# USBPD_CH211.net
KiCad netlist of a schematic drawn in Altium Designer
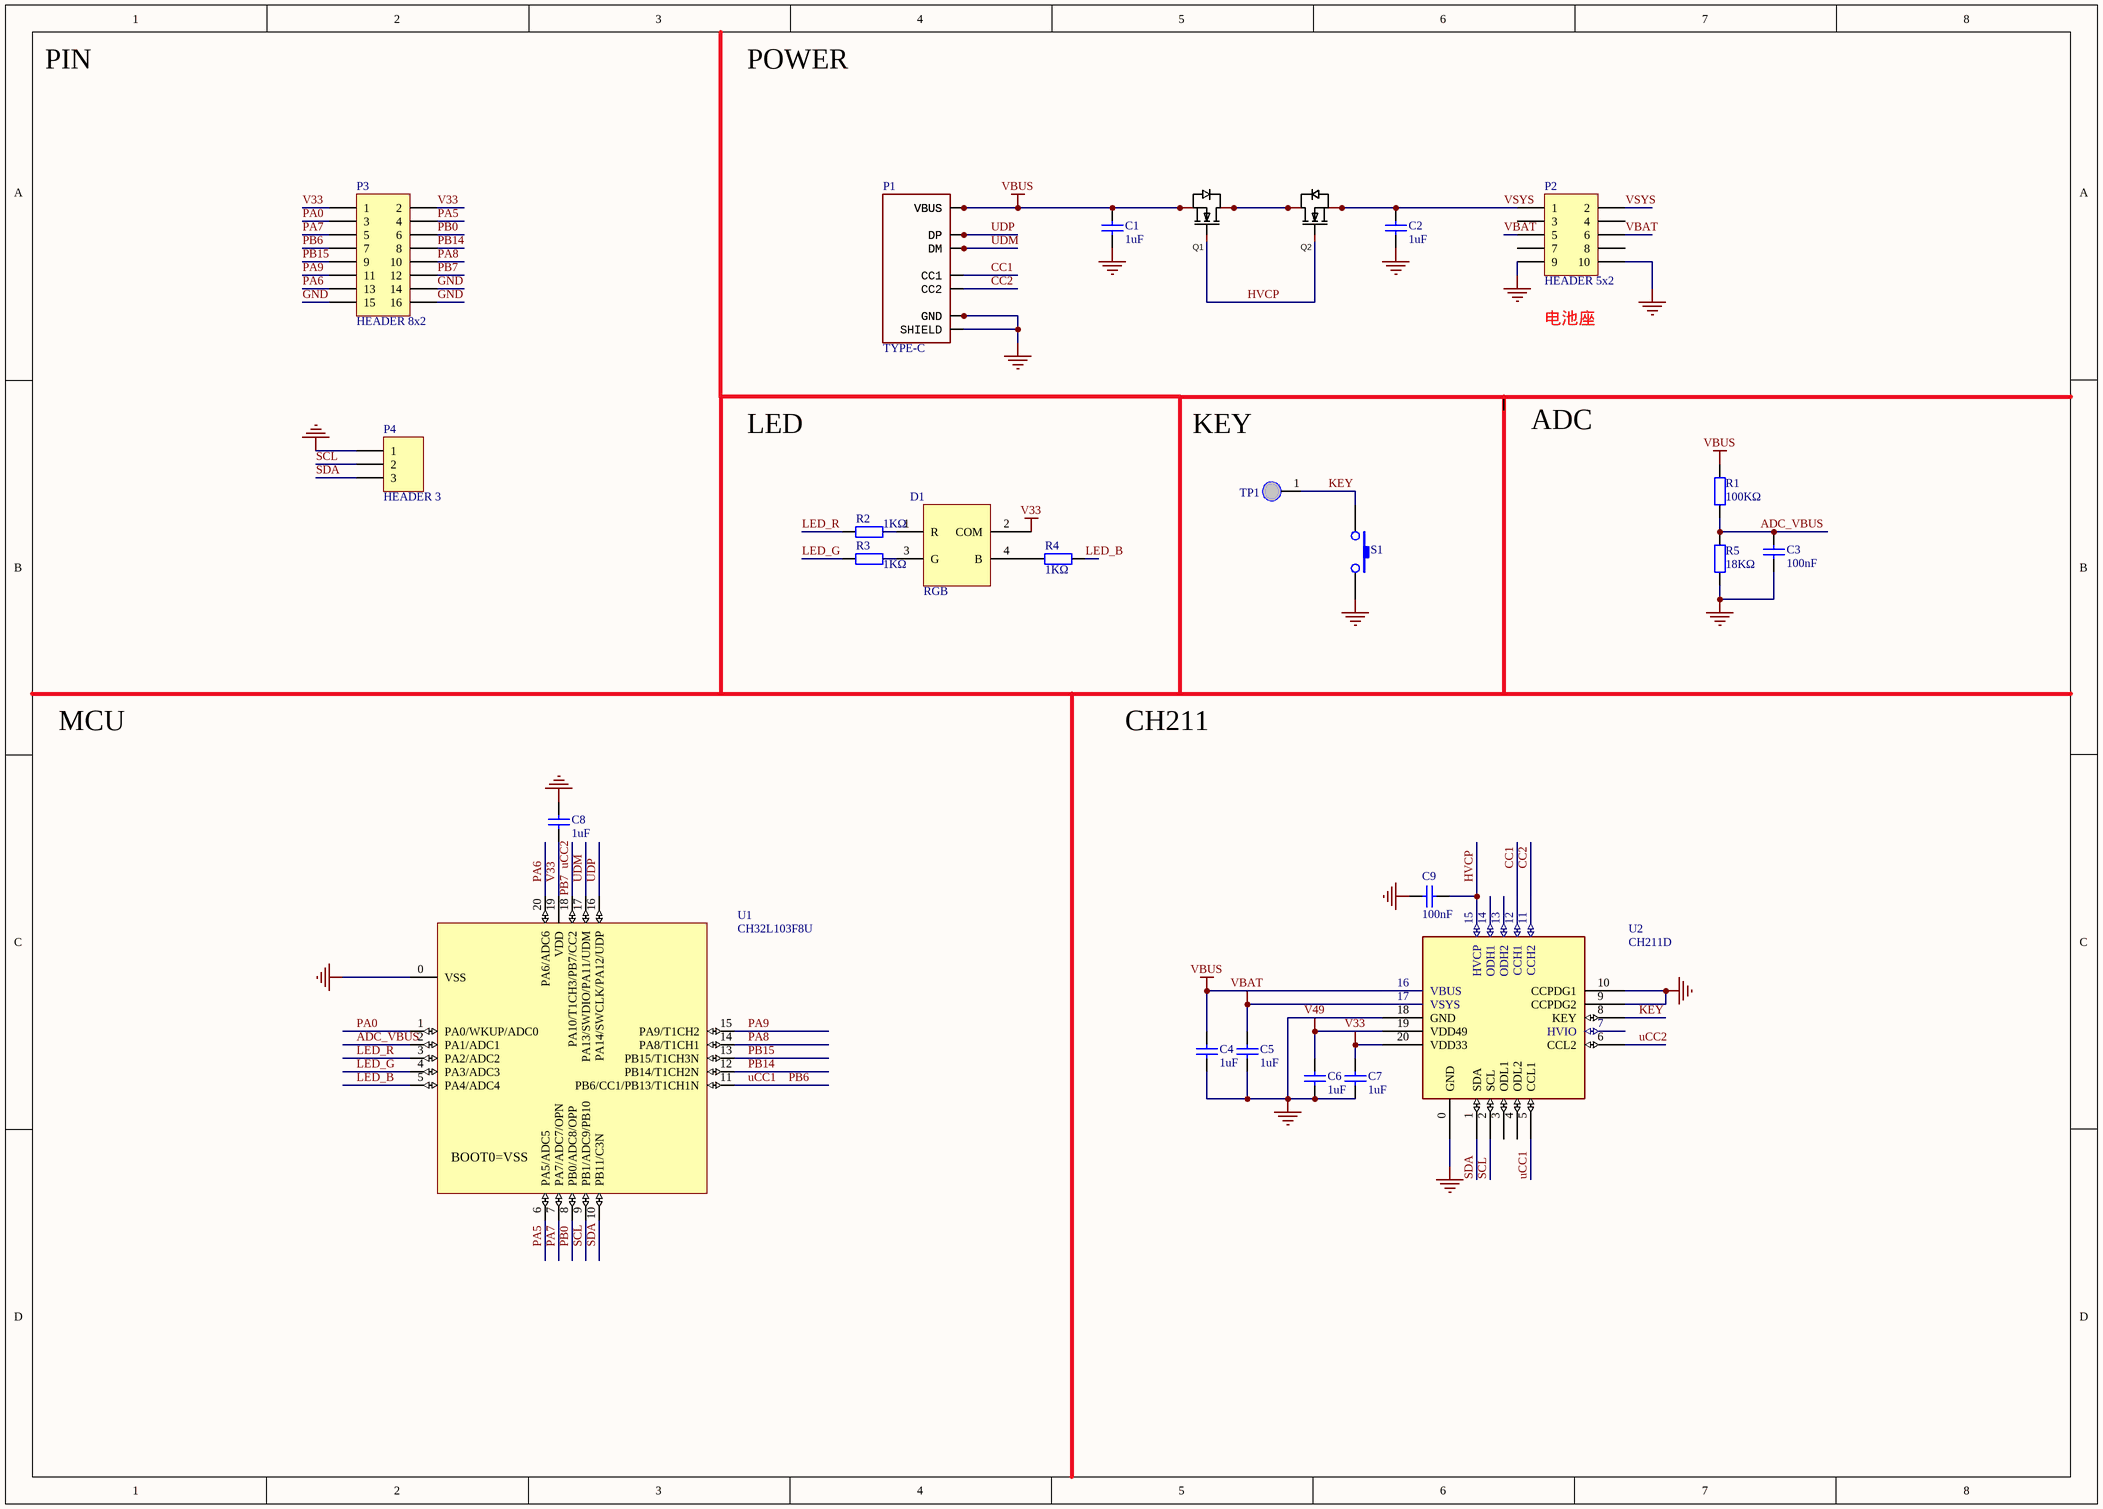
[diagram p0: USBPD_CH211.SchDoc]

(export (version "E")
  (design (tool "Eeschema 10.0.6"))
  (components
    (comp (ref "C1")
      (value "1uF")
      (footprint "0402_C")
      (description "贴片电容")
      (libsource (lib "Miscellaneous Devices LC") (part "0603 100nF (104) 10% 50V"))
    )
    (comp (ref "C2")
      (value "1uF")
      (footprint "0402_C")
      (description "贴片电容")
      (libsource (lib "Miscellaneous Devices LC") (part "0603 100nF (104) 10% 50V"))
    )
    (comp (ref "C3")
      (value "100nF")
      (footprint "0402_C")
      (description "贴片电容")
      (libsource (lib "Miscellaneous Devices LC") (part "0603 100nF (104) 10% 50V"))
    )
    (comp (ref "C4")
      (value "1uF")
      (footprint "0402_C")
      (description "贴片电容")
      (libsource (lib "Miscellaneous Devices LC") (part "0603 100nF (104) 10% 50V"))
    )
    (comp (ref "C5")
      (value "1uF")
      (footprint "0402_C")
      (description "贴片电容")
      (libsource (lib "Miscellaneous Devices LC") (part "0603 100nF (104) 10% 50V"))
    )
    (comp (ref "C6")
      (value "1uF")
      (footprint "0402_C")
      (description "贴片电容")
      (libsource (lib "Miscellaneous Devices LC") (part "0603 100nF (104) 10% 50V"))
    )
    (comp (ref "C7")
      (value "1uF")
      (footprint "0402_C")
      (description "贴片电容")
      (libsource (lib "Miscellaneous Devices LC") (part "0603 100nF (104) 10% 50V"))
    )
    (comp (ref "C8")
      (value "1uF")
      (footprint "0402_C")
      (description "贴片电容")
      (libsource (lib "Miscellaneous Devices LC") (part "0603 1uF (105) 10% 50V"))
    )
    (comp (ref "C9")
      (value "100nF")
      (footprint "0402_C")
      (description "贴片电容")
      (libsource (lib "Miscellaneous Devices LC") (part "0603 100nF (104) 10% 50V"))
    )
    (comp (ref "D1")
      (value "RGB")
      (footprint "RGB")
      (description "共阳")
      (libsource (lib "wch_sch_others") (part "RGB"))
    )
    (comp (ref "P1")
      (value "TYPE-C")
      (footprint "TYPE-C-Receptacle-2.0")
      (libsource (lib "Miscellaneous SCH Lib") (part "TYPE-C-Receptacle-RefDesign"))
    )
    (comp (ref "P2")
      (value "HEADER 5x2")
      (footprint "MYPCB:IDC10-2.54mm")
      (description "Header, 5-Pin, Dual row")
      (libsource (lib "wch_sch_others") (part "HEADER 5x2"))
    )
    (comp (ref "P3")
      (value "HEADER 8x2")
      (footprint "MYPCB:IDC16-2.54mm")
      (description "Header, 8-Pin, Dual row")
      (libsource (lib "wch_sch_others") (part "HEADER 8x2"))
    )
    (comp (ref "P4")
      (value "HEADER 3")
      (footprint "SIP3-2.54MM")
      (description "Header, 3-Pin")
      (libsource (lib "wch_sch_others") (part "HEADER 3"))
    )
    (comp (ref "Q1")
      (value "ASDM40N52E-R")
      (footprint "DFN-8_L3.1-W3.0-P0.65-LS3.3-BL")
      (description "DFN_NMOS")
      (fields (field (name "MANUFACTURER") "Ascend(安森德)"))
      (libsource (lib "Zcc") (part "NMOS_DFN3*3.1"))
    )
    (comp (ref "Q2")
      (value "ASDM40N52E-R")
      (footprint "DFN-8_L3.1-W3.0-P0.65-LS3.3-BL")
      (description "DFN_NMOS")
      (fields (field (name "MANUFACTURER") "Ascend(安森德)"))
      (libsource (lib "Zcc") (part "NMOS_DFN3*3.1"))
    )
    (comp (ref "R1")
      (value "100KΩ")
      (footprint "0402")
      (description "贴片电阻")
      (libsource (lib "Miscellaneous Devices LC") (part "0603 100KΩ (1003) 1%"))
    )
    (comp (ref "R2")
      (value "1KΩ")
      (footprint "0402")
      (description "贴片电阻")
      (libsource (lib "") (part "0603 100KΩ (1003) 1%_1"))
    )
    (comp (ref "R3")
      (value "1KΩ")
      (footprint "0402")
      (description "贴片电阻")
      (libsource (lib "") (part "0603 100KΩ (1003) 1%_1"))
    )
    (comp (ref "R4")
      (value "1KΩ")
      (footprint "0402")
      (description "贴片电阻")
      (libsource (lib "") (part "0603 100KΩ (1003) 1%_1"))
    )
    (comp (ref "R5")
      (value "18KΩ")
      (footprint "0402")
      (description "贴片电阻")
      (libsource (lib "Miscellaneous Devices LC") (part "0603 100KΩ (1003) 1%"))
    )
    (comp (ref "S1")
      (value "KEY")
      (footprint "SMD_6.1x3.65x2.5mm-KEY")
      (libsource (lib "wch_sch_others") (part "KEY1"))
    )
    (comp (ref "TP1")
      (value "Testpoint")
      (footprint "TESTPOINT3")
      (description "测试点")
      (libsource (lib "wch_sch_others") (part "Testpoint"))
    )
    (comp (ref "U1")
      (value "CH32L103F8U")
      (footprint "QFN20_3X3")
      (description "RISC-V LMD-MCU, 96MHz, USB, Type-C/PD-5K1, CAN, OPA, lower power")
      (libsource (lib "CHXXX") (part "CH32L103F8U"))
    )
    (comp (ref "U2")
      (value "CH211D")
      (footprint "QFN20_3X3")
      (description "28V USB PD & Type-C high voltage interface")
      (libsource (lib "CHXXX") (part "CH211D"))
    )
  )
  (nets
    (net (code "1") (name "/ADC_VBUS") (class "Default")
      (node (ref "C3") (pin "2") (pinfunction "2_2") (pintype "passive"))
      (node (ref "R1") (pin "2") (pinfunction "2_2") (pintype "passive"))
      (node (ref "R5") (pin "1") (pinfunction "1_1") (pintype "passive"))
      (node (ref "U1") (pin "2") (pinfunction "PA1/ADC1_2") (pintype "bidirectional"))
    )
    (net (code "2") (name "/CC1") (class "Default")
      (node (ref "P1") (pin "A5") (pinfunction "CC1_A5") (pintype "passive"))
      (node (ref "U2") (pin "12") (pinfunction "CCH1_12") (pintype "bidirectional"))
    )
    (net (code "3") (name "/CC2") (class "Default")
      (node (ref "P1") (pin "B5") (pinfunction "CC2_B5") (pintype "passive"))
      (node (ref "U2") (pin "11") (pinfunction "CCH2_11") (pintype "bidirectional"))
    )
    (net (code "4") (name "/HVCP") (class "Default")
      (node (ref "C9") (pin "1") (pinfunction "1_1") (pintype "passive"))
      (node (ref "Q1") (pin "4") (pinfunction "G_4") (pintype "passive"))
      (node (ref "Q2") (pin "4") (pinfunction "G_4") (pintype "passive"))
      (node (ref "U2") (pin "15") (pinfunction "HVCP_15") (pintype "bidirectional"))
    )
    (net (code "5") (name "/KEY") (class "Default")
      (node (ref "S1") (pin "1") (pinfunction "1_1") (pintype "passive"))
      (node (ref "TP1") (pin "1") (pintype "passive"))
      (node (ref "U2") (pin "8") (pinfunction "KEY_8") (pintype "bidirectional"))
    )
    (net (code "6") (name "/LED_B") (class "Default")
      (node (ref "R4") (pin "2") (pinfunction "2_2") (pintype "passive"))
      (node (ref "U1") (pin "5") (pinfunction "PA4/ADC4_5") (pintype "bidirectional"))
    )
    (net (code "7") (name "/LED_G") (class "Default")
      (node (ref "R3") (pin "1") (pinfunction "1_1") (pintype "passive"))
      (node (ref "U1") (pin "4") (pinfunction "PA3/ADC3_4") (pintype "bidirectional"))
    )
    (net (code "8") (name "/LED_R") (class "Default")
      (node (ref "R2") (pin "1") (pinfunction "1_1") (pintype "passive"))
      (node (ref "U1") (pin "3") (pinfunction "PA2/ADC2_3") (pintype "bidirectional"))
    )
    (net (code "9") (name "/PA0") (class "Default")
      (node (ref "P3") (pin "3") (pinfunction "3_3") (pintype "passive"))
      (node (ref "U1") (pin "1") (pinfunction "PA0/WKUP/ADC0_1") (pintype "bidirectional"))
    )
    (net (code "10") (name "/PA5") (class "Default")
      (node (ref "P3") (pin "4") (pinfunction "4_4") (pintype "passive"))
      (node (ref "U1") (pin "6") (pinfunction "PA5/ADC5_6") (pintype "bidirectional"))
    )
    (net (code "11") (name "/PA6") (class "Default")
      (node (ref "P3") (pin "13") (pinfunction "13_13") (pintype "passive"))
      (node (ref "U1") (pin "20") (pinfunction "PA6/ADC6_20") (pintype "bidirectional"))
    )
    (net (code "12") (name "/PA7") (class "Default")
      (node (ref "P3") (pin "5") (pinfunction "5_5") (pintype "passive"))
      (node (ref "U1") (pin "7") (pinfunction "PA7/ADC7/OPN_7") (pintype "bidirectional"))
    )
    (net (code "13") (name "/PA8") (class "Default")
      (node (ref "P3") (pin "10") (pinfunction "10_10") (pintype "passive"))
      (node (ref "U1") (pin "14") (pinfunction "PA8/T1CH1_14") (pintype "bidirectional"))
    )
    (net (code "14") (name "/PA9") (class "Default")
      (node (ref "P3") (pin "11") (pinfunction "11_11") (pintype "passive"))
      (node (ref "U1") (pin "15") (pinfunction "PA9/T1CH2_15") (pintype "bidirectional"))
    )
    (net (code "15") (name "/PB0") (class "Default")
      (node (ref "P3") (pin "6") (pinfunction "6_6") (pintype "passive"))
      (node (ref "U1") (pin "8") (pinfunction "PB0/ADC8/OPP_8") (pintype "bidirectional"))
    )
    (net (code "16") (name "/PB6") (class "Default")
      (node (ref "P3") (pin "7") (pinfunction "7_7") (pintype "passive"))
      (node (ref "U1") (pin "11") (pinfunction "PB6/CC1/PB13/T1CH1N_11") (pintype "bidirectional"))
      (node (ref "U2") (pin "5") (pinfunction "CCL1_5") (pintype "bidirectional"))
    )
    (net (code "17") (name "/PB7") (class "Default")
      (node (ref "P3") (pin "12") (pinfunction "12_12") (pintype "passive"))
      (node (ref "U1") (pin "18") (pinfunction "PA10/T1CH3/PB7/CC2_18") (pintype "bidirectional"))
      (node (ref "U2") (pin "6") (pinfunction "CCL2_6") (pintype "bidirectional"))
    )
    (net (code "18") (name "/PB14") (class "Default")
      (node (ref "P3") (pin "8") (pinfunction "8_8") (pintype "passive"))
      (node (ref "U1") (pin "12") (pinfunction "PB14/T1CH2N_12") (pintype "bidirectional"))
    )
    (net (code "19") (name "/PB15") (class "Default")
      (node (ref "P3") (pin "9") (pinfunction "9_9") (pintype "passive"))
      (node (ref "U1") (pin "13") (pinfunction "PB15/T1CH3N_13") (pintype "bidirectional"))
    )
    (net (code "20") (name "/SCL") (class "Default")
      (node (ref "P4") (pin "2") (pinfunction "2_2") (pintype "passive"))
      (node (ref "U1") (pin "9") (pinfunction "PB1/ADC9/PB10_9") (pintype "bidirectional"))
      (node (ref "U2") (pin "2") (pinfunction "SCL_2") (pintype "bidirectional"))
    )
    (net (code "21") (name "/SDA") (class "Default")
      (node (ref "P4") (pin "3") (pinfunction "3_3") (pintype "passive"))
      (node (ref "U1") (pin "10") (pinfunction "PB11/C3N_10") (pintype "bidirectional"))
      (node (ref "U2") (pin "1") (pinfunction "SDA_1") (pintype "bidirectional"))
    )
    (net (code "22") (name "/UDM") (class "Default")
      (node (ref "P1") (pin "A7") (pinfunction "DM_A7") (pintype "passive"))
      (node (ref "P1") (pin "B7") (pinfunction "DM_B7") (pintype "passive"))
      (node (ref "U1") (pin "17") (pinfunction "PA13/SWDIO/PA11/UDM_17") (pintype "bidirectional"))
    )
    (net (code "23") (name "/UDP") (class "Default")
      (node (ref "P1") (pin "A6") (pinfunction "DP_A6") (pintype "passive"))
      (node (ref "P1") (pin "B6") (pinfunction "DP_B6") (pintype "passive"))
      (node (ref "U1") (pin "16") (pinfunction "PA14/SWCLK/PA12/UDP_16") (pintype "bidirectional"))
    )
    (net (code "24") (name "/VSYS") (class "Default")
      (node (ref "C2") (pin "2") (pinfunction "2_2") (pintype "passive"))
      (node (ref "P2") (pin "1") (pinfunction "1_1") (pintype "passive"))
      (node (ref "P2") (pin "2") (pinfunction "2_2") (pintype "passive"))
      (node (ref "Q2") (pin "1") (pinfunction "S_1") (pintype "passive"))
      (node (ref "Q2") (pin "2") (pinfunction "S_2") (pintype "passive"))
      (node (ref "Q2") (pin "3") (pinfunction "S_3") (pintype "passive"))
    )
    (net (code "25") (name "GND") (class "Default")
      (node (ref "C1") (pin "1") (pinfunction "1_1") (pintype "passive"))
      (node (ref "C2") (pin "1") (pinfunction "1_1") (pintype "passive"))
      (node (ref "C3") (pin "1") (pinfunction "1_1") (pintype "passive"))
      (node (ref "C4") (pin "1") (pinfunction "1_1") (pintype "passive"))
      (node (ref "C5") (pin "1") (pinfunction "1_1") (pintype "passive"))
      (node (ref "C6") (pin "1") (pinfunction "1_1") (pintype "passive"))
      (node (ref "C7") (pin "1") (pinfunction "1_1") (pintype "passive"))
      (node (ref "C8") (pin "1") (pinfunction "1_1") (pintype "passive"))
      (node (ref "C9") (pin "2") (pinfunction "2_2") (pintype "passive"))
      (node (ref "P1") (pin "0") (pinfunction "SHIELD_0") (pintype "passive"))
      (node (ref "P1") (pin "A1") (pinfunction "GND_A1") (pintype "passive"))
      (node (ref "P1") (pin "A12") (pinfunction "GND_A12") (pintype "passive"))
      (node (ref "P1") (pin "B1") (pinfunction "GND_B1") (pintype "passive"))
      (node (ref "P1") (pin "B12") (pinfunction "GND_B12") (pintype "passive"))
      (node (ref "P2") (pin "10") (pinfunction "10_10") (pintype "passive"))
      (node (ref "P2") (pin "9") (pinfunction "9_9") (pintype "passive"))
      (node (ref "P3") (pin "14") (pinfunction "14_14") (pintype "passive"))
      (node (ref "P3") (pin "15") (pinfunction "15_15") (pintype "passive"))
      (node (ref "P3") (pin "16") (pinfunction "16_16") (pintype "passive"))
      (node (ref "P4") (pin "1") (pinfunction "1_1") (pintype "passive"))
      (node (ref "R5") (pin "2") (pinfunction "2_2") (pintype "passive"))
      (node (ref "S1") (pin "2") (pinfunction "2_2") (pintype "passive"))
      (node (ref "U1") (pin "0") (pinfunction "VSS_0") (pintype "power_in"))
      (node (ref "U2") (pin "0") (pinfunction "GND_0") (pintype "power_in"))
      (node (ref "U2") (pin "10") (pinfunction "CCPDG1_10") (pintype "power_in"))
      (node (ref "U2") (pin "18") (pinfunction "GND_18") (pintype "power_in"))
      (node (ref "U2") (pin "9") (pinfunction "CCPDG2_9") (pintype "power_in"))
    )
    (net (code "26") (name "Net-(D1-B)") (class "Default")
      (node (ref "D1") (pin "4") (pinfunction "B_4") (pintype "passive"))
      (node (ref "R4") (pin "1") (pinfunction "1_1") (pintype "passive"))
    )
    (net (code "27") (name "Net-(D1-G)") (class "Default")
      (node (ref "D1") (pin "3") (pinfunction "G_3") (pintype "passive"))
      (node (ref "R3") (pin "2") (pinfunction "2_2") (pintype "passive"))
    )
    (net (code "28") (name "Net-(D1-R)") (class "Default")
      (node (ref "D1") (pin "1") (pinfunction "R_1") (pintype "passive"))
      (node (ref "R2") (pin "2") (pinfunction "2_2") (pintype "passive"))
    )
    (net (code "29") (name "Net-(Q1-D-Pad5)") (class "Default")
      (node (ref "Q1") (pin "5") (pinfunction "D_5") (pintype "passive"))
      (node (ref "Q1") (pin "6") (pinfunction "D_6") (pintype "passive"))
      (node (ref "Q1") (pin "7") (pinfunction "D_7") (pintype "passive"))
      (node (ref "Q1") (pin "8") (pinfunction "D_8") (pintype "passive"))
      (node (ref "Q2") (pin "5") (pinfunction "D_5") (pintype "passive"))
      (node (ref "Q2") (pin "6") (pinfunction "D_6") (pintype "passive"))
      (node (ref "Q2") (pin "7") (pinfunction "D_7") (pintype "passive"))
      (node (ref "Q2") (pin "8") (pinfunction "D_8") (pintype "passive"))
    )
    (net (code "30") (name "V33") (class "Default")
      (node (ref "C7") (pin "2") (pinfunction "2_2") (pintype "passive"))
      (node (ref "C8") (pin "2") (pinfunction "2_2") (pintype "passive"))
      (node (ref "D1") (pin "2") (pinfunction "COM_2") (pintype "passive"))
      (node (ref "P3") (pin "1") (pinfunction "1_1") (pintype "passive"))
      (node (ref "P3") (pin "2") (pinfunction "2_2") (pintype "passive"))
      (node (ref "U1") (pin "19") (pinfunction "VDD_19") (pintype "power_in"))
      (node (ref "U2") (pin "20") (pinfunction "VDD33_20") (pintype "power_in"))
    )
    (net (code "31") (name "V49") (class "Default")
      (node (ref "C6") (pin "2") (pinfunction "2_2") (pintype "passive"))
      (node (ref "U2") (pin "19") (pinfunction "VDD49_19") (pintype "power_in"))
    )
    (net (code "32") (name "VBAT") (class "Default")
      (node (ref "C5") (pin "2") (pinfunction "2_2") (pintype "passive"))
      (node (ref "P2") (pin "5") (pinfunction "5_5") (pintype "passive"))
      (node (ref "P2") (pin "6") (pinfunction "6_6") (pintype "passive"))
      (node (ref "U2") (pin "17") (pinfunction "VSYS_17") (pintype "power_in"))
    )
    (net (code "33") (name "VBUS") (class "Default")
      (node (ref "C1") (pin "2") (pinfunction "2_2") (pintype "passive"))
      (node (ref "C4") (pin "2") (pinfunction "2_2") (pintype "passive"))
      (node (ref "P1") (pin "A4") (pinfunction "VBUS_A4") (pintype "passive"))
      (node (ref "P1") (pin "A9") (pinfunction "VBUS_A9") (pintype "passive"))
      (node (ref "P1") (pin "B4") (pinfunction "VBUS_B4") (pintype "passive"))
      (node (ref "P1") (pin "B9") (pinfunction "VBUS_B9") (pintype "passive"))
      (node (ref "Q1") (pin "1") (pinfunction "S_1") (pintype "passive"))
      (node (ref "Q1") (pin "2") (pinfunction "S_2") (pintype "passive"))
      (node (ref "Q1") (pin "3") (pinfunction "S_3") (pintype "passive"))
      (node (ref "R1") (pin "1") (pinfunction "1_1") (pintype "passive"))
      (node (ref "U2") (pin "16") (pinfunction "VBUS_16") (pintype "power_in"))
    )
    (net (code "34") (name "unconnected-(P2-Pad3)") (class "Default")
      (node (ref "P2") (pin "3") (pinfunction "3_3") (pintype "passive"))
    )
    (net (code "35") (name "unconnected-(P2-Pad4)") (class "Default")
      (node (ref "P2") (pin "4") (pinfunction "4_4") (pintype "passive"))
    )
    (net (code "36") (name "unconnected-(P2-Pad7)") (class "Default")
      (node (ref "P2") (pin "7") (pinfunction "7_7") (pintype "passive"))
    )
    (net (code "37") (name "unconnected-(P2-Pad8)") (class "Default")
      (node (ref "P2") (pin "8") (pinfunction "8_8") (pintype "passive"))
    )
    (net (code "38") (name "unconnected-(U2-HVIO-Pad7)") (class "Default")
      (node (ref "U2") (pin "7") (pinfunction "HVIO_7") (pintype "bidirectional"))
    )
    (net (code "39") (name "unconnected-(U2-ODH1-Pad14)") (class "Default")
      (node (ref "U2") (pin "14") (pinfunction "ODH1_14") (pintype "bidirectional"))
    )
    (net (code "40") (name "unconnected-(U2-ODH2-Pad13)") (class "Default")
      (node (ref "U2") (pin "13") (pinfunction "ODH2_13") (pintype "bidirectional"))
    )
    (net (code "41") (name "unconnected-(U2-ODL1-Pad3)") (class "Default")
      (node (ref "U2") (pin "3") (pinfunction "ODL1_3") (pintype "bidirectional"))
    )
    (net (code "42") (name "unconnected-(U2-ODL2-Pad4)") (class "Default")
      (node (ref "U2") (pin "4") (pinfunction "ODL2_4") (pintype "bidirectional"))
    )
  )
)
